# ISO_SPI.net
KiCad netlist of a schematic drawn in Altium Designer
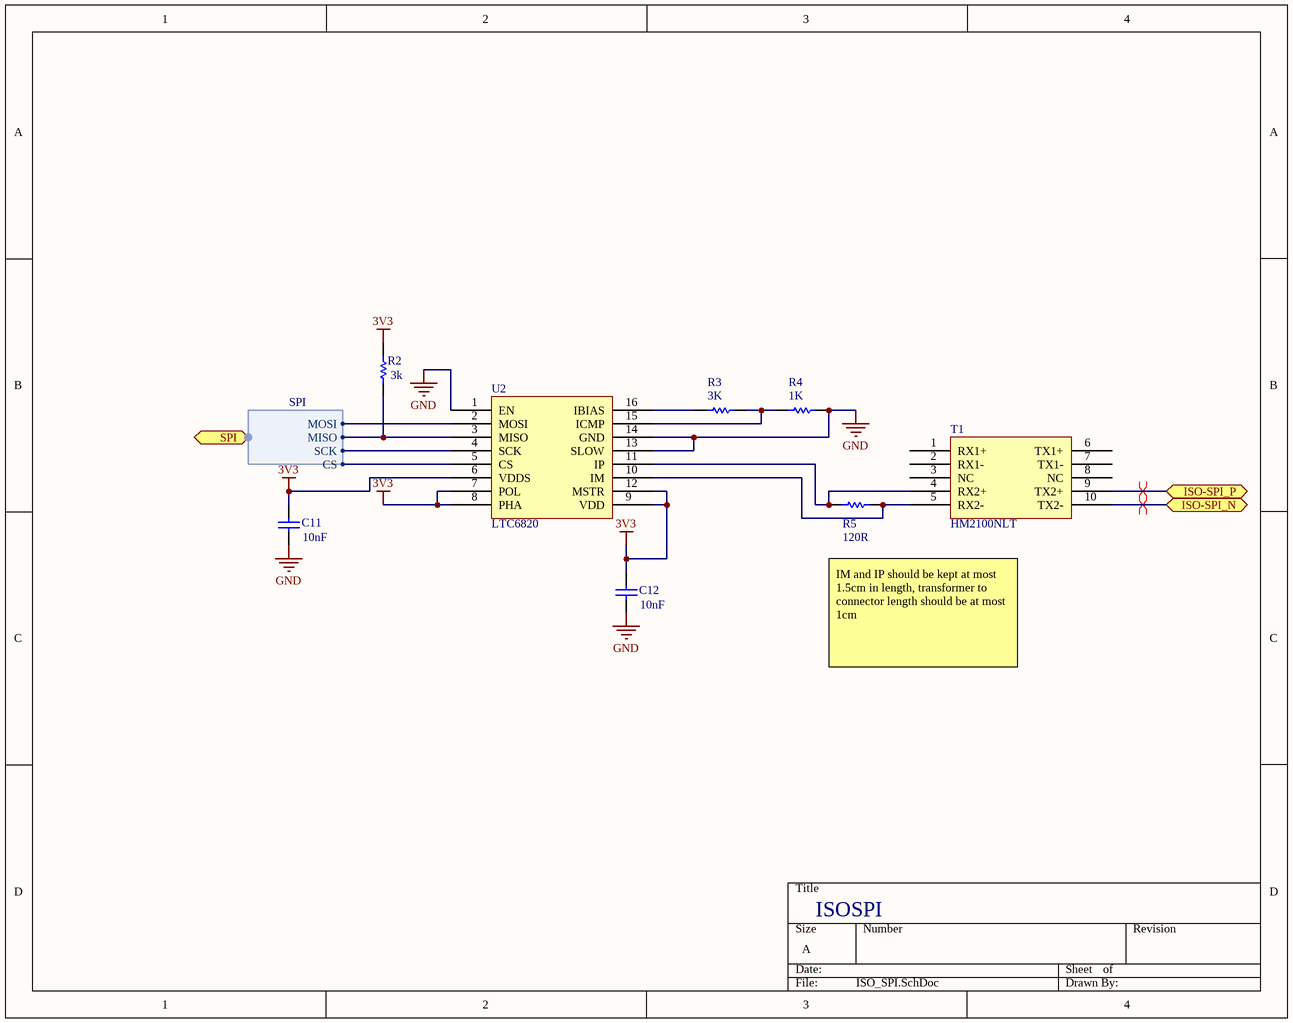
[diagram p0: ISO_SPI.SchDoc]

(export (version "E")
  (design (tool "Eeschema 10.0.6"))
  (components
    (comp (ref "C11")
      (value "10nF")
      (footprint "C0805")
      (description "C0805C103K8RAC7800. 10000pF ±10% 10V Ceramic Capacitor X7R 0805 (2012 Metric)")
      (fields (field (name "Comment") "10V") (field (name "PUBLISHER") "Altium Limited"))
      (libsource (lib "Miscellaneous Devices") (part "Cap"))
    )
    (comp (ref "C12")
      (value "10nF")
      (footprint "C0805")
      (description "C0805C103K8RAC7800. 10000pF ±10% 10V Ceramic Capacitor X7R 0805 (2012 Metric)")
      (fields (field (name "Comment") "10V") (field (name "PUBLISHER") "Altium Limited"))
      (libsource (lib "Miscellaneous Devices") (part "Cap"))
    )
    (comp (ref "R2")
      (value "3k")
      (footprint "J1-0603")
      (fields (field (name "Comment") "1%") (field (name "PUBLISHER") "Altium Limited"))
      (libsource (lib "Miscellaneous Devices") (part "Res1"))
    )
    (comp (ref "R3")
      (value "3K")
      (footprint "J1-0603")
      (fields (field (name "Comment") "1%") (field (name "PUBLISHER") "Altium Limited"))
      (libsource (lib "Miscellaneous Devices") (part "Res1"))
    )
    (comp (ref "R4")
      (value "1K")
      (footprint "J1-0603")
      (fields (field (name "Comment") "1%") (field (name "PUBLISHER") "Altium Limited"))
      (libsource (lib "Miscellaneous Devices") (part "Res1"))
    )
    (comp (ref "R5")
      (value "120R")
      (footprint "J1-0603")
      (fields (field (name "Comment") "1%") (field (name "PUBLISHER") "Altium Limited"))
      (libsource (lib "Miscellaneous Devices") (part "Res1"))
    )
    (comp (ref "T1") (value "HM2100NLT") (footprint "HM2100NLT") (libsource (lib "MCU") (part "HM2100NLT")))
    (comp (ref "U2") (value "LTC6820") (footprint "LTC6820") (libsource (lib "MCU") (part "LTC6820")))
  )
  (nets
    (net (code "2") (name "/CS") (class "Default")
      (node (ref "U2") (pin "5") (pinfunction "CS_5") (pintype "passive"))
    )
    (net (code "3") (name "/ISO-SPI_N") (class "Default")
      (node (ref "T1") (pin "10") (pinfunction "TX2-_10") (pintype "passive"))
    )
    (net (code "4") (name "/ISO-SPI_P") (class "Default")
      (node (ref "T1") (pin "9") (pinfunction "TX2+_9") (pintype "passive"))
    )
    (net (code "5") (name "/MISO") (class "Default")
      (node (ref "R2") (pin "1") (pinfunction "1_1") (pintype "passive"))
      (node (ref "U2") (pin "3") (pinfunction "MISO_3") (pintype "passive"))
    )
    (net (code "6") (name "/MOSI") (class "Default")
      (node (ref "U2") (pin "2") (pinfunction "MOSI_2") (pintype "passive"))
    )
    (net (code "7") (name "/SCK") (class "Default")
      (node (ref "U2") (pin "4") (pinfunction "SCK_4") (pintype "passive"))
    )
    (net (code "9") (name "3V3") (class "Default")
      (node (ref "C11") (pin "1") (pinfunction "1_1") (pintype "passive"))
      (node (ref "C12") (pin "1") (pinfunction "1_1") (pintype "passive"))
      (node (ref "R2") (pin "2") (pinfunction "2_2") (pintype "passive"))
      (node (ref "U2") (pin "12") (pinfunction "MSTR_12") (pintype "passive"))
      (node (ref "U2") (pin "6") (pinfunction "VDDS_6") (pintype "passive"))
      (node (ref "U2") (pin "7") (pinfunction "POL_7") (pintype "passive"))
      (node (ref "U2") (pin "8") (pinfunction "PHA_8") (pintype "passive"))
      (node (ref "U2") (pin "9") (pinfunction "VDD_9") (pintype "passive"))
    )
    (net (code "10") (name "GND") (class "Default")
      (node (ref "C11") (pin "2") (pinfunction "2_2") (pintype "passive"))
      (node (ref "C12") (pin "2") (pinfunction "2_2") (pintype "passive"))
      (node (ref "R4") (pin "2") (pinfunction "2_2") (pintype "passive"))
      (node (ref "U2") (pin "1") (pinfunction "EN_1") (pintype "passive"))
      (node (ref "U2") (pin "13") (pinfunction "SLOW_13") (pintype "passive"))
      (node (ref "U2") (pin "14") (pinfunction "GND_14") (pintype "passive"))
    )
    (net (code "11") (name "Net-(T1-RX2+)") (class "Default")
      (node (ref "R5") (pin "1") (pinfunction "1_1") (pintype "passive"))
      (node (ref "T1") (pin "4") (pinfunction "RX2+_4") (pintype "passive"))
      (node (ref "U2") (pin "11") (pinfunction "IP_11") (pintype "passive"))
    )
    (net (code "12") (name "Net-(T1-RX2-)") (class "Default")
      (node (ref "R5") (pin "2") (pinfunction "2_2") (pintype "passive"))
      (node (ref "T1") (pin "5") (pinfunction "RX2-_5") (pintype "passive"))
      (node (ref "U2") (pin "10") (pinfunction "IM_10") (pintype "passive"))
    )
    (net (code "13") (name "Net-(U2-IBIAS)") (class "Default")
      (node (ref "R3") (pin "1") (pinfunction "1_1") (pintype "passive"))
      (node (ref "U2") (pin "16") (pinfunction "IBIAS_16") (pintype "passive"))
    )
    (net (code "14") (name "Net-(U2-ICMP)") (class "Default")
      (node (ref "R3") (pin "2") (pinfunction "2_2") (pintype "passive"))
      (node (ref "R4") (pin "1") (pinfunction "1_1") (pintype "passive"))
      (node (ref "U2") (pin "15") (pinfunction "ICMP_15") (pintype "passive"))
    )
    (net (code "15") (name "unconnected-(T1-NC-Pad3)") (class "Default")
      (node (ref "T1") (pin "3") (pinfunction "NC_3") (pintype "passive"))
    )
    (net (code "16") (name "unconnected-(T1-NC-Pad8)") (class "Default")
      (node (ref "T1") (pin "8") (pinfunction "NC_8") (pintype "passive"))
    )
    (net (code "17") (name "unconnected-(T1-RX1+-Pad1)") (class "Default")
      (node (ref "T1") (pin "1") (pinfunction "RX1+_1") (pintype "passive"))
    )
    (net (code "18") (name "unconnected-(T1-RX1--Pad2)") (class "Default")
      (node (ref "T1") (pin "2") (pinfunction "RX1-_2") (pintype "passive"))
    )
    (net (code "19") (name "unconnected-(T1-TX1+-Pad6)") (class "Default")
      (node (ref "T1") (pin "6") (pinfunction "TX1+_6") (pintype "passive"))
    )
    (net (code "20") (name "unconnected-(T1-TX1--Pad7)") (class "Default")
      (node (ref "T1") (pin "7") (pinfunction "TX1-_7") (pintype "passive"))
    )
  )
)
